# SPECCY2010.net
KiCad netlist of a schematic drawn in Altium Designer
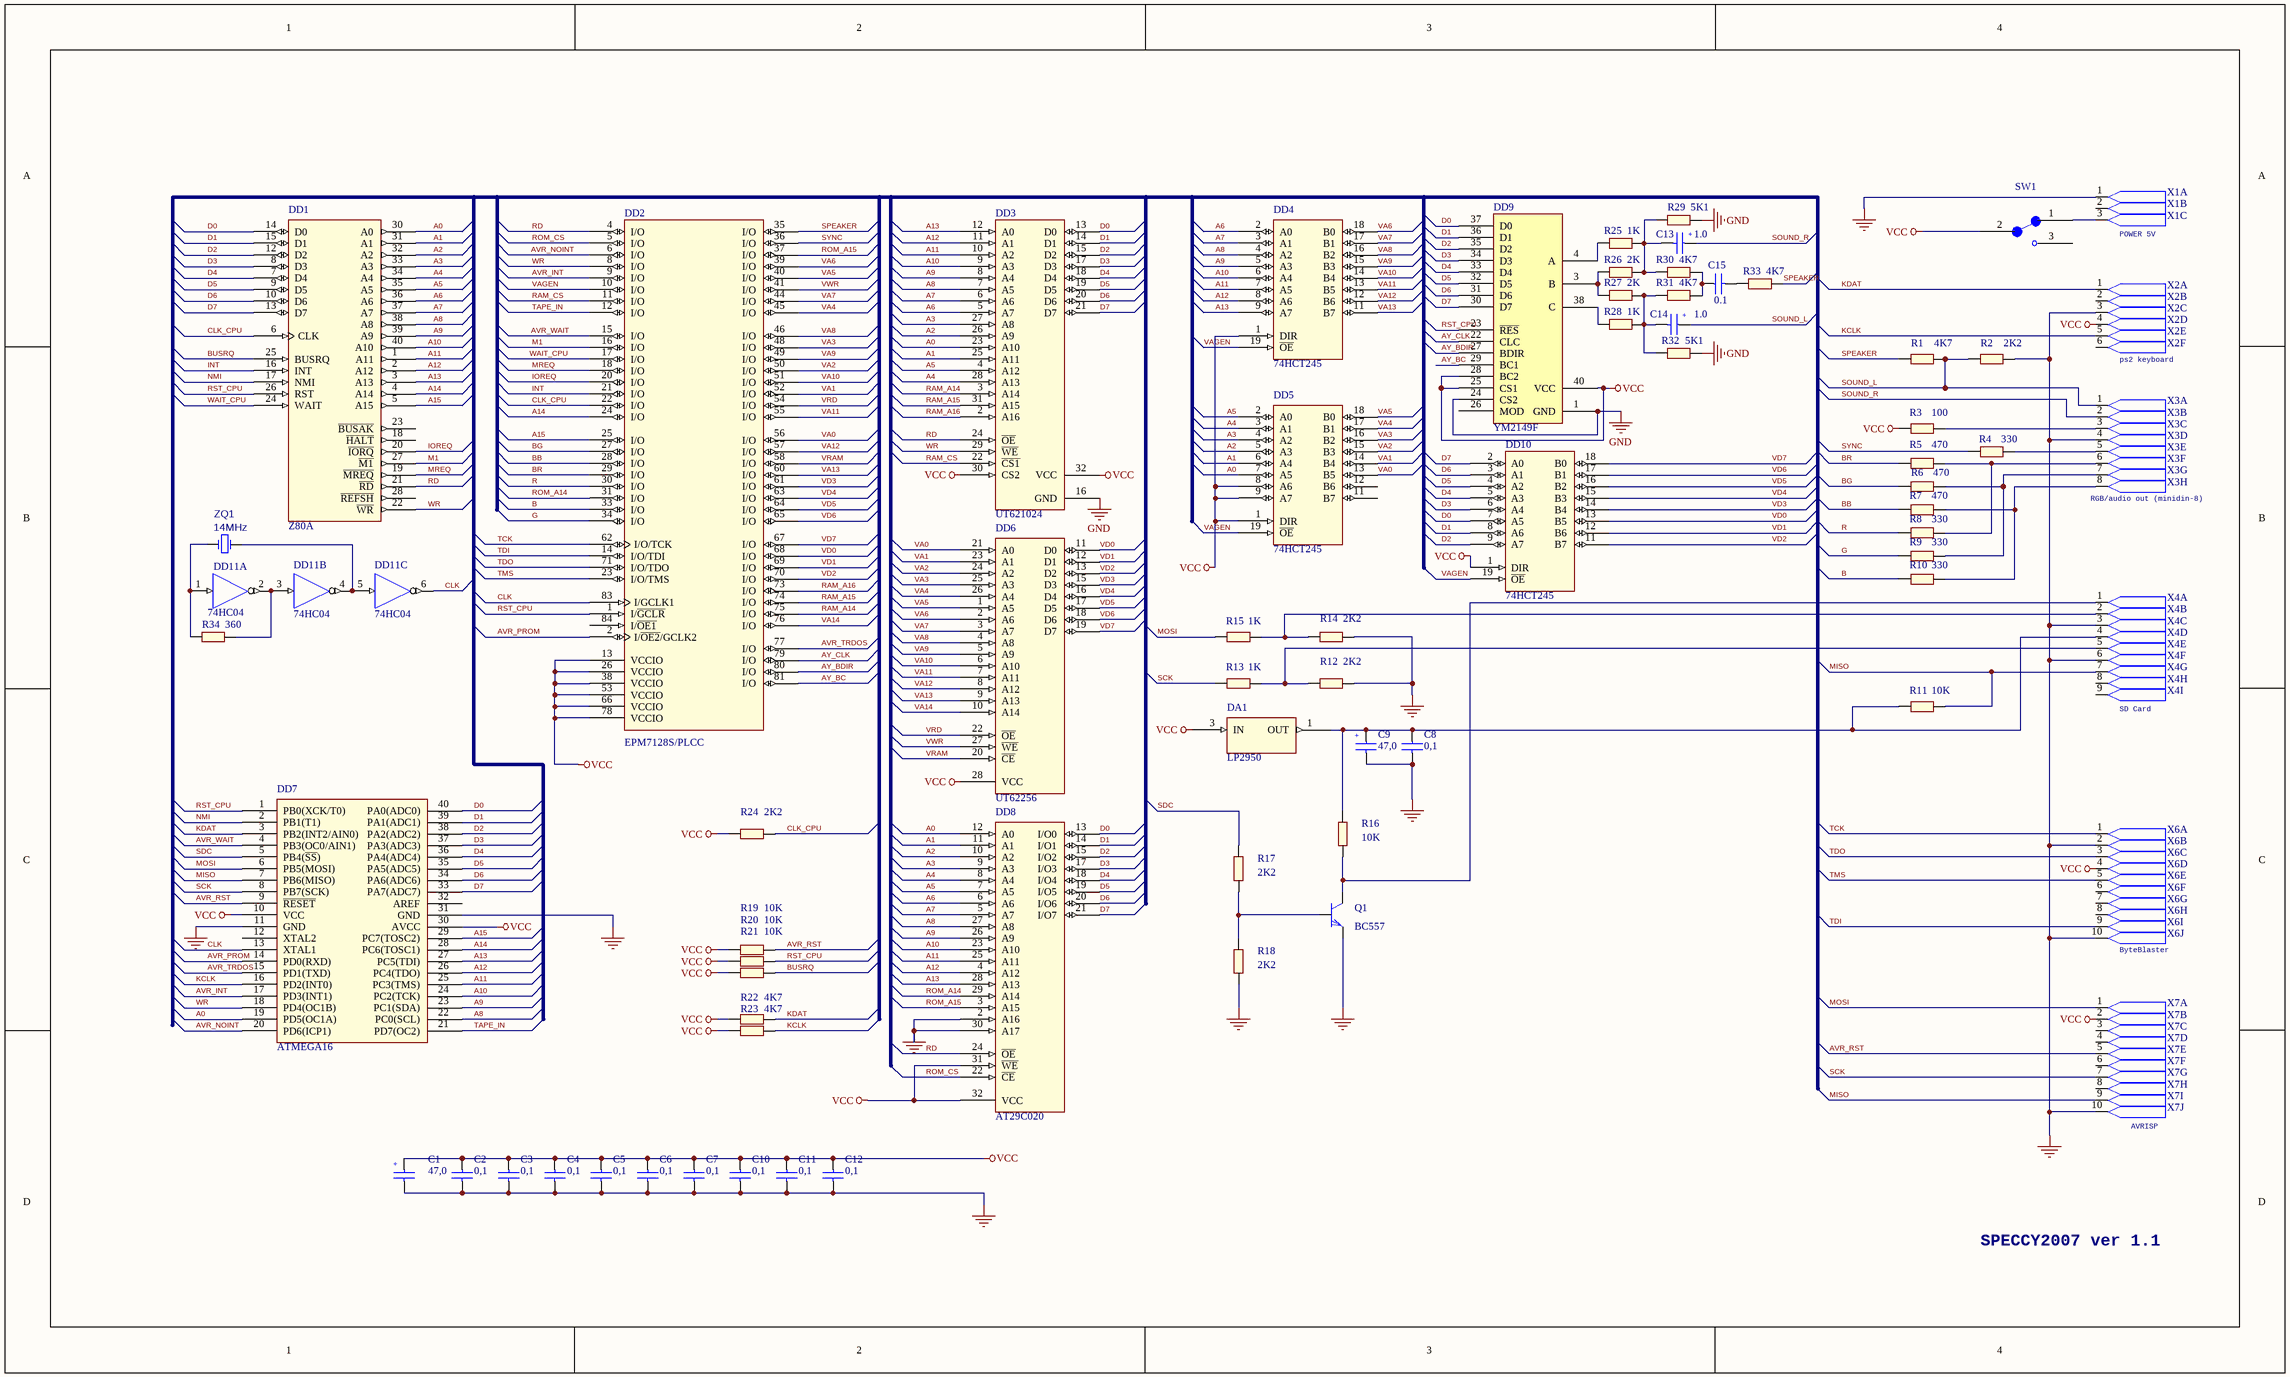
[diagram p0: SPECCY2010.SchDoc]

(export (version "E")
  (design (tool "Eeschema 10.0.6"))
  (components
    (comp (ref "C1")
      (value "47,0")
      (footprint "CAPPOL_2.54")
      (libsource (lib "SPECCY2007_Library") (part "C POL"))
    )
    (comp (ref "C2")
      (value "0,1")
      (footprint "CAP_5.08-7.8x3.2")
      (libsource (lib "SPECCY2007_Library") (part "C"))
    )
    (comp (ref "C3")
      (value "0,1")
      (footprint "CAP_5.08-7.8x3.2")
      (libsource (lib "SPECCY2007_Library") (part "C"))
    )
    (comp (ref "C4")
      (value "0,1")
      (footprint "CAP_5.08-7.8x3.2")
      (libsource (lib "SPECCY2007_Library") (part "C"))
    )
    (comp (ref "C5")
      (value "0,1")
      (footprint "CAP_5.08-7.8x3.2")
      (libsource (lib "SPECCY2007_Library") (part "C"))
    )
    (comp (ref "C6")
      (value "0,1")
      (footprint "CAP_5.08-7.8x3.2")
      (libsource (lib "SPECCY2007_Library") (part "C"))
    )
    (comp (ref "C7")
      (value "0,1")
      (footprint "CAP_5.08-7.8x3.2")
      (libsource (lib "SPECCY2007_Library") (part "C"))
    )
    (comp (ref "C8")
      (value "0,1")
      (footprint "CAP_5.08-7.8x3.2")
      (libsource (lib "SPECCY2007_Library") (part "C"))
    )
    (comp (ref "C9")
      (value "47,0")
      (footprint "CAPPOL_2.54")
      (libsource (lib "SPECCY2007_Library") (part "C POL"))
    )
    (comp (ref "C10")
      (value "0,1")
      (footprint "CAP_5.08-7.8x3.2")
      (libsource (lib "SPECCY2007_Library") (part "C"))
    )
    (comp (ref "C11")
      (value "0,1")
      (footprint "CAP_5.08-7.8x3.2")
      (libsource (lib "SPECCY2007_Library") (part "C"))
    )
    (comp (ref "C12")
      (value "0,1")
      (footprint "CAP_5.08-7.8x3.2")
      (libsource (lib "SPECCY2007_Library") (part "C"))
    )
    (comp (ref "C13")
      (value "1.0")
      (footprint "CAPPOL_2.54")
      (libsource (lib "SPECCY2010_Library") (part "C POL"))
    )
    (comp (ref "C14")
      (value "1.0")
      (footprint "CAPPOL_2.54")
      (libsource (lib "SPECCY2010_Library") (part "C POL"))
    )
    (comp (ref "C15")
      (value "0.1")
      (footprint "CAP_5.08-7.8x3.2")
      (libsource (lib "SPECCY2010_Library") (part "C"))
    )
    (comp (ref "DA1")
      (value "LP2950")
      (footprint "TO92")
      (libsource (lib "SPECCY2007_Library") (part "LP2950"))
    )
    (comp (ref "DD1")
      (value "Z80A")
      (footprint "DIP-40")
      (libsource (lib "SPECCY2007_Library") (part "Z80A"))
    )
    (comp (ref "DD2")
      (value "EPM7128S/PLCC")
      (footprint "PLCC84-Socket+AlteraMAX700S")
      (libsource (lib "SPECCY2007_Library") (part "EPM7128S/PLCC"))
    )
    (comp (ref "DD3")
      (value "UT621024")
      (footprint "DIP-32/D41.2")
      (libsource (lib "SPECCY2010_Library") (part "UT621024"))
    )
    (comp (ref "DD4")
      (value "74HCT245")
      (footprint "DIP-20")
      (libsource (lib "SPECCY2007_Library") (part "74HCT245"))
    )
    (comp (ref "DD5")
      (value "74HCT245")
      (footprint "DIP-20")
      (libsource (lib "SPECCY2007_Library") (part "74HCT245"))
    )
    (comp (ref "DD6")
      (value "UT62256")
      (footprint "DIP-28W")
      (libsource (lib "SPECCY2010_Library") (part "CY62256_Syd's"))
    )
    (comp (ref "DD7")
      (value "ATMEGA16")
      (footprint "DIP-40")
      (libsource (lib "SPECCY2007_Library") (part "ATMEGA16"))
    )
    (comp (ref "DD8")
      (value "AT29C020")
      (footprint "DIP-32/D41.2")
      (libsource (lib "SPECCY2007_Library") (part "AT29C020"))
    )
    (comp (ref "DD9")
      (value "YM2149F")
      (footprint "DIP-40")
      (libsource (lib "SPECCY2010_Library") (part "YM2149F"))
    )
    (comp (ref "DD10")
      (value "74HCT245")
      (footprint "DIP-20")
      (libsource (lib "SPECCY2010_Library") (part "74HCT245"))
    )
    (comp (ref "DD11")
      (value "74HC04")
      (footprint "DIP-14")
      (description "Hex Inverter")
      (fields (field (name "PUBLISHER") "Altium Limited"))
      (libsource (lib "SPECCY2010_Library") (part "74HC04"))
    )
    (comp (ref "Q1")
      (value "BC557")
      (footprint "TO92")
      (libsource (lib "SPECCY2007_Library") (part "TRANS NPN"))
    )
    (comp (ref "R1") (value "4K7") (footprint "RES_10.16") (libsource (lib "") (part "R_1")))
    (comp (ref "R2") (value "2K2") (footprint "RES_10.16") (libsource (lib "") (part "R_1")))
    (comp (ref "R3") (value "100") (footprint "RES_10.16") (libsource (lib "") (part "R_1")))
    (comp (ref "R4") (value "330") (footprint "RES_10.16") (libsource (lib "") (part "R_1")))
    (comp (ref "R5") (value "470") (footprint "RES_10.16") (libsource (lib "") (part "R_1")))
    (comp (ref "R6") (value "470") (footprint "RES_10.16") (libsource (lib "") (part "R_1")))
    (comp (ref "R7") (value "470") (footprint "RES_10.16") (libsource (lib "") (part "R_1")))
    (comp (ref "R8") (value "330") (footprint "RES_10.16") (libsource (lib "") (part "R_1")))
    (comp (ref "R9") (value "330") (footprint "RES_10.16") (libsource (lib "") (part "R_1")))
    (comp (ref "R10") (value "330") (footprint "RES_10.16") (libsource (lib "") (part "R_1")))
    (comp (ref "R11") (value "10K") (footprint "RES_10.16") (libsource (lib "") (part "R_1")))
    (comp (ref "R12") (value "2K2") (footprint "RES_10.16") (libsource (lib "") (part "R_1")))
    (comp (ref "R13") (value "1K") (footprint "RES_10.16") (libsource (lib "") (part "R_1")))
    (comp (ref "R14") (value "2K2") (footprint "RES_10.16") (libsource (lib "") (part "R_1")))
    (comp (ref "R15") (value "1K") (footprint "RES_10.16") (libsource (lib "") (part "R_1")))
    (comp (ref "R16") (value "10K") (footprint "RES_10.16") (libsource (lib "SPECCY2007_Library") (part "R")))
    (comp (ref "R17") (value "2K2") (footprint "RES_10.16") (libsource (lib "SPECCY2007_Library") (part "R")))
    (comp (ref "R18") (value "2K2") (footprint "RES_10.16") (libsource (lib "SPECCY2007_Library") (part "R")))
    (comp (ref "R19") (value "10K") (footprint "RES_10.16") (libsource (lib "") (part "R_1")))
    (comp (ref "R20") (value "10K") (footprint "RES_10.16") (libsource (lib "") (part "R_1")))
    (comp (ref "R21") (value "10K") (footprint "RES_10.16") (libsource (lib "") (part "R_1")))
    (comp (ref "R22") (value "4K7") (footprint "RES_10.16") (libsource (lib "") (part "R_1")))
    (comp (ref "R23") (value "4K7") (footprint "RES_10.16") (libsource (lib "") (part "R_1")))
    (comp (ref "R24") (value "2K2") (footprint "RES_10.16") (libsource (lib "") (part "R_1")))
    (comp (ref "R25") (value "1K") (footprint "RES_10.16") (libsource (lib "SPECCY2010_Library") (part "R")))
    (comp (ref "R26") (value "2K") (footprint "RES_10.16") (libsource (lib "SPECCY2010_Library") (part "R")))
    (comp (ref "R27") (value "2K") (footprint "RES_10.16") (libsource (lib "SPECCY2010_Library") (part "R")))
    (comp (ref "R28") (value "1K") (footprint "RES_10.16") (libsource (lib "SPECCY2010_Library") (part "R")))
    (comp (ref "R29") (value "5K1") (footprint "RES_10.16") (libsource (lib "SPECCY2010_Library") (part "R")))
    (comp (ref "R30") (value "4K7") (footprint "RES_10.16") (libsource (lib "SPECCY2010_Library") (part "R")))
    (comp (ref "R31") (value "4K7") (footprint "RES_10.16") (libsource (lib "SPECCY2010_Library") (part "R")))
    (comp (ref "R32") (value "5K1") (footprint "RES_10.16") (libsource (lib "SPECCY2010_Library") (part "R")))
    (comp (ref "R33") (value "4K7") (footprint "RES_10.16") (libsource (lib "SPECCY2010_Library") (part "R")))
    (comp (ref "R34") (value "360") (footprint "RES_10.16") (libsource (lib "SPECCY2010_Library") (part "R")))
    (comp (ref "SW1")
      (value "SW_T_SPDT")
      (footprint "SW_T_SPDT")
      (libsource (lib "SPECCY2007_Library") (part "SW_T_SPDT"))
    )
    (comp (ref "X1")
      (value "X3")
      (footprint "CONN JACK PWR")
      (libsource (lib "SPECCY2007_Library") (part "X3"))
    )
    (comp (ref "X2") (value "X6") (footprint "Mini-DIN6") (libsource (lib "SPECCY2007_Library") (part "X6")))
    (comp (ref "X3") (value "X8") (footprint "Mini-DIN8") (libsource (lib "SPECCY2007_Library") (part "X8")))
    (comp (ref "X4")
      (value "X9")
      (footprint "SD Card socket")
      (description "SD Card socket")
      (libsource (lib "SPECCY2007_Library") (part "X9"))
    )
    (comp (ref "X6")
      (value "X10")
      (footprint "Double row pin strip 5 way")
      (libsource (lib "SPECCY2007_Library") (part "X10"))
    )
    (comp (ref "X7")
      (value "X10")
      (footprint "Double row pin strip 5 way")
      (libsource (lib "SPECCY2007_Library") (part "X10"))
    )
    (comp (ref "ZQ1")
      (value "14MHz")
      (footprint "QUARTZ")
      (description "QUARTZ")
      (libsource (lib "SPECCY2010_Library") (part "QUARTZ"))
    )
  )
  (nets
    (net (code "1") (name "/A0") (class "Default")
      (node (ref "DD1") (pin "30") (pinfunction "A0_30") (pintype "output"))
      (node (ref "DD3") (pin "23") (pinfunction "A10_23") (pintype "input"))
      (node (ref "DD5") (pin "7") (pinfunction "A5_7") (pintype "bidirectional"))
      (node (ref "DD7") (pin "19") (pinfunction "PD5(OC1A)_19") (pintype "passive"))
      (node (ref "DD8") (pin "12") (pinfunction "A0_12") (pintype "input"))
    )
    (net (code "2") (name "/A1") (class "Default")
      (node (ref "DD1") (pin "31") (pinfunction "A1_31") (pintype "output"))
      (node (ref "DD3") (pin "25") (pinfunction "A11_25") (pintype "input"))
      (node (ref "DD5") (pin "6") (pinfunction "A4_6") (pintype "bidirectional"))
      (node (ref "DD8") (pin "11") (pinfunction "A1_11") (pintype "input"))
    )
    (net (code "3") (name "/A2") (class "Default")
      (node (ref "DD1") (pin "32") (pinfunction "A2_32") (pintype "output"))
      (node (ref "DD3") (pin "26") (pinfunction "A9_26") (pintype "input"))
      (node (ref "DD5") (pin "5") (pinfunction "A3_5") (pintype "bidirectional"))
      (node (ref "DD8") (pin "10") (pinfunction "A2_10") (pintype "input"))
    )
    (net (code "4") (name "/A3") (class "Default")
      (node (ref "DD1") (pin "33") (pinfunction "A3_33") (pintype "output"))
      (node (ref "DD3") (pin "27") (pinfunction "A8_27") (pintype "input"))
      (node (ref "DD5") (pin "4") (pinfunction "A2_4") (pintype "bidirectional"))
      (node (ref "DD8") (pin "9") (pinfunction "A3_9") (pintype "input"))
    )
    (net (code "5") (name "/A4") (class "Default")
      (node (ref "DD1") (pin "34") (pinfunction "A4_34") (pintype "output"))
      (node (ref "DD3") (pin "28") (pinfunction "A13_28") (pintype "input"))
      (node (ref "DD5") (pin "3") (pinfunction "A1_3") (pintype "bidirectional"))
      (node (ref "DD8") (pin "8") (pinfunction "A4_8") (pintype "input"))
    )
    (net (code "6") (name "/A5") (class "Default")
      (node (ref "DD1") (pin "35") (pinfunction "A5_35") (pintype "output"))
      (node (ref "DD3") (pin "4") (pinfunction "A12_4") (pintype "input"))
      (node (ref "DD5") (pin "2") (pinfunction "A0_2") (pintype "bidirectional"))
      (node (ref "DD8") (pin "7") (pinfunction "A5_7") (pintype "input"))
    )
    (net (code "7") (name "/A6") (class "Default")
      (node (ref "DD1") (pin "36") (pinfunction "A6_36") (pintype "output"))
      (node (ref "DD3") (pin "5") (pinfunction "A7_5") (pintype "input"))
      (node (ref "DD4") (pin "2") (pinfunction "A0_2") (pintype "bidirectional"))
      (node (ref "DD8") (pin "6") (pinfunction "A6_6") (pintype "input"))
    )
    (net (code "8") (name "/A7") (class "Default")
      (node (ref "DD1") (pin "37") (pinfunction "A7_37") (pintype "output"))
      (node (ref "DD3") (pin "6") (pinfunction "A6_6") (pintype "input"))
      (node (ref "DD4") (pin "3") (pinfunction "A1_3") (pintype "bidirectional"))
      (node (ref "DD8") (pin "5") (pinfunction "A7_5") (pintype "input"))
    )
    (net (code "9") (name "/A8") (class "Default")
      (node (ref "DD1") (pin "38") (pinfunction "A8_38") (pintype "output"))
      (node (ref "DD3") (pin "7") (pinfunction "A5_7") (pintype "input"))
      (node (ref "DD4") (pin "4") (pinfunction "A2_4") (pintype "bidirectional"))
      (node (ref "DD7") (pin "22") (pinfunction "PC0(SCL)_22") (pintype "passive"))
      (node (ref "DD8") (pin "27") (pinfunction "A8_27") (pintype "input"))
    )
    (net (code "10") (name "/A9") (class "Default")
      (node (ref "DD1") (pin "39") (pinfunction "A9_39") (pintype "output"))
      (node (ref "DD3") (pin "8") (pinfunction "A4_8") (pintype "input"))
      (node (ref "DD4") (pin "5") (pinfunction "A3_5") (pintype "bidirectional"))
      (node (ref "DD7") (pin "23") (pinfunction "PC1(SDA)_23") (pintype "passive"))
      (node (ref "DD8") (pin "26") (pinfunction "A9_26") (pintype "input"))
    )
    (net (code "11") (name "/A10") (class "Default")
      (node (ref "DD1") (pin "40") (pinfunction "A10_40") (pintype "output"))
      (node (ref "DD3") (pin "9") (pinfunction "A3_9") (pintype "input"))
      (node (ref "DD4") (pin "6") (pinfunction "A4_6") (pintype "bidirectional"))
      (node (ref "DD7") (pin "24") (pinfunction "PC2(TCK)_24") (pintype "passive"))
      (node (ref "DD8") (pin "23") (pinfunction "A10_23") (pintype "input"))
    )
    (net (code "12") (name "/A11") (class "Default")
      (node (ref "DD1") (pin "1") (pinfunction "A11_1") (pintype "output"))
      (node (ref "DD3") (pin "10") (pinfunction "A2_10") (pintype "input"))
      (node (ref "DD4") (pin "7") (pinfunction "A5_7") (pintype "bidirectional"))
      (node (ref "DD7") (pin "25") (pinfunction "PC3(TMS)_25") (pintype "passive"))
      (node (ref "DD8") (pin "25") (pinfunction "A11_25") (pintype "input"))
    )
    (net (code "13") (name "/A12") (class "Default")
      (node (ref "DD1") (pin "2") (pinfunction "A12_2") (pintype "output"))
      (node (ref "DD3") (pin "11") (pinfunction "A1_11") (pintype "input"))
      (node (ref "DD4") (pin "8") (pinfunction "A6_8") (pintype "bidirectional"))
      (node (ref "DD7") (pin "26") (pinfunction "PC4(TDO)_26") (pintype "passive"))
      (node (ref "DD8") (pin "4") (pinfunction "A12_4") (pintype "input"))
    )
    (net (code "14") (name "/A13") (class "Default")
      (node (ref "DD1") (pin "3") (pinfunction "A13_3") (pintype "output"))
      (node (ref "DD3") (pin "12") (pinfunction "A0_12") (pintype "input"))
      (node (ref "DD4") (pin "9") (pinfunction "A7_9") (pintype "bidirectional"))
      (node (ref "DD7") (pin "27") (pinfunction "PC5(TDI)_27") (pintype "passive"))
      (node (ref "DD8") (pin "28") (pinfunction "A13_28") (pintype "input"))
    )
    (net (code "15") (name "/A14") (class "Default")
      (node (ref "DD1") (pin "4") (pinfunction "A14_4") (pintype "output"))
      (node (ref "DD2") (pin "24") (pinfunction "I/O_24") (pintype "bidirectional"))
      (node (ref "DD7") (pin "28") (pinfunction "PC6(TOSC1)_28") (pintype "passive"))
    )
    (net (code "16") (name "/A15") (class "Default")
      (node (ref "DD1") (pin "5") (pinfunction "A15_5") (pintype "output"))
      (node (ref "DD2") (pin "25") (pinfunction "I/O_25") (pintype "bidirectional"))
      (node (ref "DD7") (pin "29") (pinfunction "PC7(TOSC2)_29") (pintype "passive"))
    )
    (net (code "17") (name "/AVR_INT") (class "Default")
      (node (ref "DD2") (pin "9") (pinfunction "I/O_9") (pintype "bidirectional"))
      (node (ref "DD7") (pin "17") (pinfunction "PD3(INT1)_17") (pintype "passive"))
    )
    (net (code "18") (name "/AVR_NOINT") (class "Default")
      (node (ref "DD2") (pin "6") (pinfunction "I/O_6") (pintype "bidirectional"))
      (node (ref "DD7") (pin "20") (pinfunction "PD6(ICP1)_20") (pintype "passive"))
    )
    (net (code "19") (name "/AVR_PROM") (class "Default")
      (node (ref "DD2") (pin "2") (pinfunction "I/~{OE2}/GCLK2_2") (pintype "bidirectional"))
      (node (ref "DD7") (pin "14") (pinfunction "PD0(RXD)_14") (pintype "passive"))
    )
    (net (code "20") (name "/AVR_RST") (class "Default")
      (node (ref "DD7") (pin "9") (pinfunction "~{RESET}_9") (pintype "passive"))
      (node (ref "R19") (pin "2") (pinfunction "2_2") (pintype "passive"))
      (node (ref "X7") (pin "5") (pinfunction "CON_5") (pintype "passive"))
    )
    (net (code "21") (name "/AVR_TRDOS") (class "Default")
      (node (ref "DD2") (pin "77") (pinfunction "I/O_77") (pintype "bidirectional"))
      (node (ref "DD7") (pin "15") (pinfunction "PD1(TXD)_15") (pintype "passive"))
    )
    (net (code "22") (name "/AVR_WAIT") (class "Default")
      (node (ref "DD2") (pin "15") (pinfunction "I/O_15") (pintype "bidirectional"))
      (node (ref "DD7") (pin "4") (pinfunction "PB3(OC0/AIN1)_4") (pintype "passive"))
    )
    (net (code "23") (name "/AY_BC") (class "Default")
      (node (ref "DD2") (pin "81") (pinfunction "I/O_81") (pintype "bidirectional"))
      (node (ref "DD9") (pin "29") (pinfunction "BC1_29") (pintype "passive"))
    )
    (net (code "24") (name "/AY_BDIR") (class "Default")
      (node (ref "DD2") (pin "80") (pinfunction "I/O_80") (pintype "bidirectional"))
      (node (ref "DD9") (pin "27") (pinfunction "BDIR_27") (pintype "passive"))
    )
    (net (code "25") (name "/AY_CLK") (class "Default")
      (node (ref "DD2") (pin "79") (pinfunction "I/O_79") (pintype "bidirectional"))
      (node (ref "DD9") (pin "22") (pinfunction "CLC_22") (pintype "passive"))
    )
    (net (code "26") (name "/B") (class "Default")
      (node (ref "DD2") (pin "33") (pinfunction "I/O_33") (pintype "bidirectional"))
      (node (ref "R10") (pin "1") (pinfunction "1_1") (pintype "passive"))
    )
    (net (code "27") (name "/BB") (class "Default")
      (node (ref "DD2") (pin "28") (pinfunction "I/O_28") (pintype "bidirectional"))
      (node (ref "R7") (pin "1") (pinfunction "1_1") (pintype "passive"))
    )
    (net (code "28") (name "/BG") (class "Default")
      (node (ref "DD2") (pin "27") (pinfunction "I/O_27") (pintype "bidirectional"))
      (node (ref "R6") (pin "1") (pinfunction "1_1") (pintype "passive"))
    )
    (net (code "29") (name "/BR") (class "Default")
      (node (ref "DD2") (pin "29") (pinfunction "I/O_29") (pintype "bidirectional"))
      (node (ref "R5") (pin "1") (pinfunction "1_1") (pintype "passive"))
    )
    (net (code "30") (name "/BUSRQ") (class "Default")
      (node (ref "DD1") (pin "25") (pinfunction "BUSRQ_25") (pintype "input"))
      (node (ref "R21") (pin "2") (pinfunction "2_2") (pintype "passive"))
    )
    (net (code "31") (name "/CLK") (class "Default")
      (node (ref "DD11") (pin "6") (pinfunction "Y_6") (pintype "output"))
      (node (ref "DD2") (pin "83") (pinfunction "I/GCLK1_83") (pintype "input"))
      (node (ref "DD7") (pin "13") (pinfunction "XTAL1_13") (pintype "passive"))
    )
    (net (code "32") (name "/CLK_CPU") (class "Default")
      (node (ref "DD1") (pin "6") (pinfunction "CLK_6") (pintype "input"))
      (node (ref "DD2") (pin "22") (pinfunction "I/O_22") (pintype "bidirectional"))
      (node (ref "R24") (pin "2") (pinfunction "2_2") (pintype "passive"))
    )
    (net (code "33") (name "/D0") (class "Default")
      (node (ref "DD1") (pin "14") (pinfunction "D0_14") (pintype "bidirectional"))
      (node (ref "DD10") (pin "7") (pinfunction "A5_7") (pintype "bidirectional"))
      (node (ref "DD3") (pin "13") (pinfunction "D0_13") (pintype "bidirectional"))
      (node (ref "DD7") (pin "40") (pinfunction "PA0(ADC0)_40") (pintype "passive"))
      (node (ref "DD8") (pin "13") (pinfunction "I/O0_13") (pintype "bidirectional"))
      (node (ref "DD9") (pin "37") (pinfunction "D0_37") (pintype "passive"))
    )
    (net (code "34") (name "/D1") (class "Default")
      (node (ref "DD1") (pin "15") (pinfunction "D1_15") (pintype "bidirectional"))
      (node (ref "DD10") (pin "8") (pinfunction "A6_8") (pintype "bidirectional"))
      (node (ref "DD3") (pin "14") (pinfunction "D1_14") (pintype "bidirectional"))
      (node (ref "DD7") (pin "39") (pinfunction "PA1(ADC1)_39") (pintype "passive"))
      (node (ref "DD8") (pin "14") (pinfunction "I/O1_14") (pintype "bidirectional"))
      (node (ref "DD9") (pin "36") (pinfunction "D1_36") (pintype "passive"))
    )
    (net (code "35") (name "/D2") (class "Default")
      (node (ref "DD1") (pin "12") (pinfunction "D2_12") (pintype "bidirectional"))
      (node (ref "DD10") (pin "9") (pinfunction "A7_9") (pintype "bidirectional"))
      (node (ref "DD3") (pin "15") (pinfunction "D2_15") (pintype "bidirectional"))
      (node (ref "DD7") (pin "38") (pinfunction "PA2(ADC2)_38") (pintype "passive"))
      (node (ref "DD8") (pin "15") (pinfunction "I/O2_15") (pintype "bidirectional"))
      (node (ref "DD9") (pin "35") (pinfunction "D2_35") (pintype "passive"))
    )
    (net (code "36") (name "/D3") (class "Default")
      (node (ref "DD1") (pin "8") (pinfunction "D3_8") (pintype "bidirectional"))
      (node (ref "DD10") (pin "6") (pinfunction "A4_6") (pintype "bidirectional"))
      (node (ref "DD3") (pin "17") (pinfunction "D3_17") (pintype "bidirectional"))
      (node (ref "DD7") (pin "37") (pinfunction "PA3(ADC3)_37") (pintype "passive"))
      (node (ref "DD8") (pin "17") (pinfunction "I/O3_17") (pintype "bidirectional"))
      (node (ref "DD9") (pin "34") (pinfunction "D3_34") (pintype "passive"))
    )
    (net (code "37") (name "/D4") (class "Default")
      (node (ref "DD1") (pin "7") (pinfunction "D4_7") (pintype "bidirectional"))
      (node (ref "DD10") (pin "5") (pinfunction "A3_5") (pintype "bidirectional"))
      (node (ref "DD3") (pin "18") (pinfunction "D4_18") (pintype "bidirectional"))
      (node (ref "DD7") (pin "36") (pinfunction "PA4(ADC4)_36") (pintype "passive"))
      (node (ref "DD8") (pin "18") (pinfunction "I/O4_18") (pintype "bidirectional"))
      (node (ref "DD9") (pin "33") (pinfunction "D4_33") (pintype "passive"))
    )
    (net (code "38") (name "/D5") (class "Default")
      (node (ref "DD1") (pin "9") (pinfunction "D5_9") (pintype "bidirectional"))
      (node (ref "DD10") (pin "4") (pinfunction "A2_4") (pintype "bidirectional"))
      (node (ref "DD3") (pin "19") (pinfunction "D5_19") (pintype "bidirectional"))
      (node (ref "DD7") (pin "35") (pinfunction "PA5(ADC5)_35") (pintype "passive"))
      (node (ref "DD8") (pin "19") (pinfunction "I/O5_19") (pintype "bidirectional"))
      (node (ref "DD9") (pin "32") (pinfunction "D5_32") (pintype "passive"))
    )
    (net (code "39") (name "/D6") (class "Default")
      (node (ref "DD1") (pin "10") (pinfunction "D6_10") (pintype "bidirectional"))
      (node (ref "DD10") (pin "3") (pinfunction "A1_3") (pintype "bidirectional"))
      (node (ref "DD3") (pin "20") (pinfunction "D6_20") (pintype "bidirectional"))
      (node (ref "DD7") (pin "34") (pinfunction "PA6(ADC6)_34") (pintype "passive"))
      (node (ref "DD8") (pin "20") (pinfunction "I/O6_20") (pintype "bidirectional"))
      (node (ref "DD9") (pin "31") (pinfunction "D6_31") (pintype "passive"))
    )
    (net (code "40") (name "/D7") (class "Default")
      (node (ref "DD1") (pin "13") (pinfunction "D7_13") (pintype "bidirectional"))
      (node (ref "DD10") (pin "2") (pinfunction "A0_2") (pintype "bidirectional"))
      (node (ref "DD3") (pin "21") (pinfunction "D7_21") (pintype "bidirectional"))
      (node (ref "DD7") (pin "33") (pinfunction "PA7(ADC7)_33") (pintype "passive"))
      (node (ref "DD8") (pin "21") (pinfunction "I/O7_21") (pintype "bidirectional"))
      (node (ref "DD9") (pin "30") (pinfunction "D7_30") (pintype "passive"))
    )
    (net (code "41") (name "/G") (class "Default")
      (node (ref "DD2") (pin "34") (pinfunction "I/O_34") (pintype "bidirectional"))
      (node (ref "R9") (pin "1") (pinfunction "1_1") (pintype "passive"))
    )
    (net (code "42") (name "/INT") (class "Default")
      (node (ref "DD1") (pin "16") (pinfunction "INT_16") (pintype "input"))
      (node (ref "DD2") (pin "21") (pinfunction "I/O_21") (pintype "bidirectional"))
    )
    (net (code "43") (name "/IOREQ") (class "Default")
      (node (ref "DD1") (pin "20") (pinfunction "~{IORQ}_20") (pintype "output"))
      (node (ref "DD2") (pin "20") (pinfunction "I/O_20") (pintype "bidirectional"))
    )
    (net (code "44") (name "/KCLK") (class "Default")
      (node (ref "DD7") (pin "16") (pinfunction "PD2(INT0)_16") (pintype "passive"))
      (node (ref "R23") (pin "2") (pinfunction "2_2") (pintype "passive"))
      (node (ref "X2") (pin "5") (pinfunction "CON_5") (pintype "passive"))
    )
    (net (code "45") (name "/KDAT") (class "Default")
      (node (ref "DD7") (pin "3") (pinfunction "PB2(INT2/AIN0)_3") (pintype "passive"))
      (node (ref "R22") (pin "2") (pinfunction "2_2") (pintype "passive"))
      (node (ref "X2") (pin "1") (pinfunction "CON_1") (pintype "passive"))
    )
    (net (code "46") (name "/M1") (class "Default")
      (node (ref "DD1") (pin "27") (pinfunction "~{M1}_27") (pintype "output"))
      (node (ref "DD2") (pin "16") (pinfunction "I/O_16") (pintype "bidirectional"))
    )
    (net (code "47") (name "/MISO") (class "Default")
      (node (ref "DD7") (pin "7") (pinfunction "PB6(MISO)_7") (pintype "passive"))
      (node (ref "R11") (pin "2") (pinfunction "2_2") (pintype "passive"))
      (node (ref "X4") (pin "7") (pinfunction "CON_7") (pintype "passive"))
      (node (ref "X7") (pin "9") (pinfunction "CON_9") (pintype "passive"))
    )
    (net (code "48") (name "/MOSI") (class "Default")
      (node (ref "DD7") (pin "6") (pinfunction "PB5(MOSI)_6") (pintype "passive"))
      (node (ref "R15") (pin "1") (pinfunction "1_1") (pintype "passive"))
      (node (ref "X7") (pin "1") (pinfunction "CON_1") (pintype "passive"))
    )
    (net (code "49") (name "/MREQ") (class "Default")
      (node (ref "DD1") (pin "19") (pinfunction "~{MREQ}_19") (pintype "output"))
      (node (ref "DD2") (pin "18") (pinfunction "I/O_18") (pintype "bidirectional"))
    )
    (net (code "50") (name "/NMI") (class "Default")
      (node (ref "DD1") (pin "17") (pinfunction "NMI_17") (pintype "input"))
      (node (ref "DD7") (pin "2") (pinfunction "PB1(T1)_2") (pintype "passive"))
    )
    (net (code "51") (name "/R") (class "Default")
      (node (ref "DD2") (pin "30") (pinfunction "I/O_30") (pintype "bidirectional"))
      (node (ref "R8") (pin "1") (pinfunction "1_1") (pintype "passive"))
    )
    (net (code "52") (name "/RAM_A14") (class "Default")
      (node (ref "DD2") (pin "75") (pinfunction "I/O_75") (pintype "bidirectional"))
      (node (ref "DD3") (pin "3") (pinfunction "A14_3") (pintype "input"))
    )
    (net (code "53") (name "/RAM_A15") (class "Default")
      (node (ref "DD2") (pin "74") (pinfunction "I/O_74") (pintype "bidirectional"))
      (node (ref "DD3") (pin "31") (pinfunction "A15_31") (pintype "input"))
    )
    (net (code "54") (name "/RAM_A16") (class "Default")
      (node (ref "DD2") (pin "73") (pinfunction "I/O_73") (pintype "bidirectional"))
      (node (ref "DD3") (pin "2") (pinfunction "A16_2") (pintype "input"))
    )
    (net (code "55") (name "/RAM_CS") (class "Default")
      (node (ref "DD2") (pin "11") (pinfunction "I/O_11") (pintype "bidirectional"))
      (node (ref "DD3") (pin "22") (pinfunction "~{CS1}_22") (pintype "input"))
    )
    (net (code "56") (name "/RD") (class "Default")
      (node (ref "DD1") (pin "21") (pinfunction "~{RD}_21") (pintype "output"))
      (node (ref "DD2") (pin "4") (pinfunction "I/O_4") (pintype "bidirectional"))
      (node (ref "DD3") (pin "24") (pinfunction "~{OE}_24") (pintype "input"))
      (node (ref "DD8") (pin "24") (pinfunction "~{OE}_24") (pintype "input"))
    )
    (net (code "57") (name "/ROM_A14") (class "Default")
      (node (ref "DD2") (pin "31") (pinfunction "I/O_31") (pintype "bidirectional"))
      (node (ref "DD8") (pin "29") (pinfunction "A14_29") (pintype "input"))
    )
    (net (code "58") (name "/ROM_A15") (class "Default")
      (node (ref "DD2") (pin "37") (pinfunction "I/O_37") (pintype "bidirectional"))
      (node (ref "DD8") (pin "3") (pinfunction "A15_3") (pintype "input"))
    )
    (net (code "59") (name "/ROM_CS") (class "Default")
      (node (ref "DD2") (pin "5") (pinfunction "I/O_5") (pintype "bidirectional"))
      (node (ref "DD8") (pin "22") (pinfunction "~{CE}_22") (pintype "input"))
    )
    (net (code "60") (name "/RST_CPU") (class "Default")
      (node (ref "DD1") (pin "26") (pinfunction "RST_26") (pintype "input"))
      (node (ref "DD2") (pin "1") (pinfunction "I/~{GCLR}_1") (pintype "input"))
      (node (ref "DD7") (pin "1") (pinfunction "PB0(XCK/T0)_1") (pintype "passive"))
      (node (ref "DD9") (pin "23") (pinfunction "~{RES}_23") (pintype "passive"))
      (node (ref "R20") (pin "2") (pinfunction "2_2") (pintype "passive"))
    )
    (net (code "61") (name "/SCK") (class "Default")
      (node (ref "DD7") (pin "8") (pinfunction "PB7(SCK)_8") (pintype "passive"))
      (node (ref "R13") (pin "1") (pinfunction "1_1") (pintype "passive"))
      (node (ref "X7") (pin "7") (pinfunction "CON_7") (pintype "passive"))
    )
    (net (code "62") (name "/SDC") (class "Default")
      (node (ref "DD7") (pin "5") (pinfunction "PB4(~{SS})_5") (pintype "passive"))
      (node (ref "R17") (pin "2") (pinfunction "2_2") (pintype "passive"))
    )
    (net (code "63") (name "/SOUND_L") (class "Default")
      (node (ref "C14") (pin "PLUS") (pinfunction "PLUS_PLUS") (pintype "passive"))
      (node (ref "R1") (pin "2") (pinfunction "2_2") (pintype "passive"))
      (node (ref "R2") (pin "1") (pinfunction "1_1") (pintype "passive"))
      (node (ref "X3") (pin "1") (pinfunction "CON_1") (pintype "passive"))
    )
    (net (code "64") (name "/SOUND_R") (class "Default")
      (node (ref "C13") (pin "PLUS") (pinfunction "PLUS_PLUS") (pintype "passive"))
      (node (ref "X3") (pin "2") (pinfunction "CON_2") (pintype "passive"))
    )
    (net (code "65") (name "/SPEAKER") (class "Default")
      (node (ref "DD2") (pin "35") (pinfunction "I/O_35") (pintype "bidirectional"))
      (node (ref "R1") (pin "1") (pinfunction "1_1") (pintype "passive"))
      (node (ref "R33") (pin "2") (pinfunction "2_2") (pintype "passive"))
    )
    (net (code "66") (name "/SYNC") (class "Default")
      (node (ref "DD2") (pin "36") (pinfunction "I/O_36") (pintype "bidirectional"))
      (node (ref "R4") (pin "1") (pinfunction "1_1") (pintype "passive"))
    )
    (net (code "67") (name "/TAPE_IN") (class "Default")
      (node (ref "DD2") (pin "12") (pinfunction "I/O_12") (pintype "bidirectional"))
      (node (ref "DD7") (pin "21") (pinfunction "PD7(OC2)_21") (pintype "passive"))
    )
    (net (code "68") (name "/TCK") (class "Default")
      (node (ref "DD2") (pin "62") (pinfunction "I/O/TCK_62") (pintype "bidirectional"))
      (node (ref "X6") (pin "1") (pinfunction "CON_1") (pintype "passive"))
    )
    (net (code "69") (name "/TDI") (class "Default")
      (node (ref "DD2") (pin "14") (pinfunction "I/O/TDI_14") (pintype "bidirectional"))
      (node (ref "X6") (pin "9") (pinfunction "CON_9") (pintype "passive"))
    )
    (net (code "70") (name "/TDO") (class "Default")
      (node (ref "DD2") (pin "71") (pinfunction "I/O/TDO_71") (pintype "bidirectional"))
      (node (ref "X6") (pin "3") (pinfunction "CON_3") (pintype "passive"))
    )
    (net (code "71") (name "/TMS") (class "Default")
      (node (ref "DD2") (pin "23") (pinfunction "I/O/TMS_23") (pintype "bidirectional"))
      (node (ref "X6") (pin "5") (pinfunction "CON_5") (pintype "passive"))
    )
    (net (code "72") (name "/VA0") (class "Default")
      (node (ref "DD2") (pin "56") (pinfunction "I/O_56") (pintype "bidirectional"))
      (node (ref "DD5") (pin "13") (pinfunction "B5_13") (pintype "bidirectional"))
      (node (ref "DD6") (pin "21") (pinfunction "A0_21") (pintype "input"))
    )
    (net (code "73") (name "/VA1") (class "Default")
      (node (ref "DD2") (pin "52") (pinfunction "I/O_52") (pintype "bidirectional"))
      (node (ref "DD5") (pin "14") (pinfunction "B4_14") (pintype "bidirectional"))
      (node (ref "DD6") (pin "23") (pinfunction "A1_23") (pintype "input"))
    )
    (net (code "74") (name "/VA2") (class "Default")
      (node (ref "DD2") (pin "50") (pinfunction "I/O_50") (pintype "bidirectional"))
      (node (ref "DD5") (pin "15") (pinfunction "B3_15") (pintype "bidirectional"))
      (node (ref "DD6") (pin "24") (pinfunction "A2_24") (pintype "input"))
    )
    (net (code "75") (name "/VA3") (class "Default")
      (node (ref "DD2") (pin "48") (pinfunction "I/O_48") (pintype "bidirectional"))
      (node (ref "DD5") (pin "16") (pinfunction "B2_16") (pintype "bidirectional"))
      (node (ref "DD6") (pin "25") (pinfunction "A3_25") (pintype "input"))
    )
    (net (code "76") (name "/VA4") (class "Default")
      (node (ref "DD2") (pin "45") (pinfunction "I/O_45") (pintype "bidirectional"))
      (node (ref "DD5") (pin "17") (pinfunction "B1_17") (pintype "bidirectional"))
      (node (ref "DD6") (pin "26") (pinfunction "A4_26") (pintype "input"))
    )
    (net (code "77") (name "/VA5") (class "Default")
      (node (ref "DD2") (pin "40") (pinfunction "I/O_40") (pintype "bidirectional"))
      (node (ref "DD5") (pin "18") (pinfunction "B0_18") (pintype "bidirectional"))
      (node (ref "DD6") (pin "1") (pinfunction "A5_1") (pintype "input"))
    )
    (net (code "78") (name "/VA6") (class "Default")
      (node (ref "DD2") (pin "39") (pinfunction "I/O_39") (pintype "bidirectional"))
      (node (ref "DD4") (pin "18") (pinfunction "B0_18") (pintype "bidirectional"))
      (node (ref "DD6") (pin "2") (pinfunction "A6_2") (pintype "input"))
    )
    (net (code "79") (name "/VA7") (class "Default")
      (node (ref "DD2") (pin "44") (pinfunction "I/O_44") (pintype "bidirectional"))
      (node (ref "DD4") (pin "17") (pinfunction "B1_17") (pintype "bidirectional"))
      (node (ref "DD6") (pin "3") (pinfunction "A7_3") (pintype "input"))
    )
    (net (code "80") (name "/VA8") (class "Default")
      (node (ref "DD2") (pin "46") (pinfunction "I/O_46") (pintype "bidirectional"))
      (node (ref "DD4") (pin "16") (pinfunction "B2_16") (pintype "bidirectional"))
      (node (ref "DD6") (pin "4") (pinfunction "A8_4") (pintype "input"))
    )
    (net (code "81") (name "/VA9") (class "Default")
      (node (ref "DD2") (pin "49") (pinfunction "I/O_49") (pintype "bidirectional"))
      (node (ref "DD4") (pin "15") (pinfunction "B3_15") (pintype "bidirectional"))
      (node (ref "DD6") (pin "5") (pinfunction "A9_5") (pintype "input"))
    )
    (net (code "82") (name "/VA10") (class "Default")
      (node (ref "DD2") (pin "51") (pinfunction "I/O_51") (pintype "bidirectional"))
      (node (ref "DD4") (pin "14") (pinfunction "B4_14") (pintype "bidirectional"))
      (node (ref "DD6") (pin "6") (pinfunction "A10_6") (pintype "input"))
    )
    (net (code "83") (name "/VA11") (class "Default")
      (node (ref "DD2") (pin "55") (pinfunction "I/O_55") (pintype "bidirectional"))
      (node (ref "DD4") (pin "13") (pinfunction "B5_13") (pintype "bidirectional"))
      (node (ref "DD6") (pin "7") (pinfunction "A11_7") (pintype "input"))
    )
    (net (code "84") (name "/VA12") (class "Default")
      (node (ref "DD2") (pin "57") (pinfunction "I/O_57") (pintype "bidirectional"))
      (node (ref "DD4") (pin "12") (pinfunction "B6_12") (pintype "bidirectional"))
      (node (ref "DD6") (pin "8") (pinfunction "A12_8") (pintype "input"))
    )
    (net (code "85") (name "/VA13") (class "Default")
      (node (ref "DD2") (pin "60") (pinfunction "I/O_60") (pintype "bidirectional"))
      (node (ref "DD4") (pin "11") (pinfunction "B7_11") (pintype "bidirectional"))
      (node (ref "DD6") (pin "9") (pinfunction "A13_9") (pintype "input"))
    )
    (net (code "86") (name "/VA14") (class "Default")
      (node (ref "DD2") (pin "76") (pinfunction "I/O_76") (pintype "bidirectional"))
      (node (ref "DD6") (pin "10") (pinfunction "A14_10") (pintype "input"))
    )
    (net (code "87") (name "/VAGEN") (class "Default")
      (node (ref "DD10") (pin "19") (pinfunction "~{OE}_19") (pintype "input"))
      (node (ref "DD2") (pin "10") (pinfunction "I/O_10") (pintype "bidirectional"))
      (node (ref "DD4") (pin "19") (pinfunction "~{OE}_19") (pintype "input"))
      (node (ref "DD5") (pin "19") (pinfunction "~{OE}_19") (pintype "input"))
    )
    (net (code "88") (name "/VD0") (class "Default")
      (node (ref "DD10") (pin "13") (pinfunction "B5_13") (pintype "bidirectional"))
      (node (ref "DD2") (pin "68") (pinfunction "I/O_68") (pintype "bidirectional"))
      (node (ref "DD6") (pin "11") (pinfunction "D0_11") (pintype "bidirectional"))
    )
    (net (code "89") (name "/VD1") (class "Default")
      (node (ref "DD10") (pin "12") (pinfunction "B6_12") (pintype "bidirectional"))
      (node (ref "DD2") (pin "69") (pinfunction "I/O_69") (pintype "bidirectional"))
      (node (ref "DD6") (pin "12") (pinfunction "D1_12") (pintype "bidirectional"))
    )
    (net (code "90") (name "/VD2") (class "Default")
      (node (ref "DD10") (pin "11") (pinfunction "B7_11") (pintype "bidirectional"))
      (node (ref "DD2") (pin "70") (pinfunction "I/O_70") (pintype "bidirectional"))
      (node (ref "DD6") (pin "13") (pinfunction "D2_13") (pintype "bidirectional"))
    )
    (net (code "91") (name "/VD3") (class "Default")
      (node (ref "DD10") (pin "14") (pinfunction "B4_14") (pintype "bidirectional"))
      (node (ref "DD2") (pin "61") (pinfunction "I/O_61") (pintype "bidirectional"))
      (node (ref "DD6") (pin "15") (pinfunction "D3_15") (pintype "bidirectional"))
    )
    (net (code "92") (name "/VD4") (class "Default")
      (node (ref "DD10") (pin "15") (pinfunction "B3_15") (pintype "bidirectional"))
      (node (ref "DD2") (pin "63") (pinfunction "I/O_63") (pintype "bidirectional"))
      (node (ref "DD6") (pin "16") (pinfunction "D4_16") (pintype "bidirectional"))
    )
    (net (code "93") (name "/VD5") (class "Default")
      (node (ref "DD10") (pin "16") (pinfunction "B2_16") (pintype "bidirectional"))
      (node (ref "DD2") (pin "64") (pinfunction "I/O_64") (pintype "bidirectional"))
      (node (ref "DD6") (pin "17") (pinfunction "D5_17") (pintype "bidirectional"))
    )
    (net (code "94") (name "/VD6") (class "Default")
      (node (ref "DD10") (pin "17") (pinfunction "B1_17") (pintype "bidirectional"))
      (node (ref "DD2") (pin "65") (pinfunction "I/O_65") (pintype "bidirectional"))
      (node (ref "DD6") (pin "18") (pinfunction "D6_18") (pintype "bidirectional"))
    )
    (net (code "95") (name "/VD7") (class "Default")
      (node (ref "DD10") (pin "18") (pinfunction "B0_18") (pintype "bidirectional"))
      (node (ref "DD2") (pin "67") (pinfunction "I/O_67") (pintype "bidirectional"))
      (node (ref "DD6") (pin "19") (pinfunction "D7_19") (pintype "bidirectional"))
    )
    (net (code "96") (name "/VRAM") (class "Default")
      (node (ref "DD2") (pin "58") (pinfunction "I/O_58") (pintype "bidirectional"))
      (node (ref "DD6") (pin "20") (pinfunction "~{CE}_20") (pintype "input"))
    )
    (net (code "97") (name "/VRD") (class "Default")
      (node (ref "DD2") (pin "54") (pinfunction "I/O_54") (pintype "bidirectional"))
      (node (ref "DD6") (pin "22") (pinfunction "~{OE}_22") (pintype "input"))
    )
    (net (code "98") (name "/VWR") (class "Default")
      (node (ref "DD2") (pin "41") (pinfunction "I/O_41") (pintype "bidirectional"))
      (node (ref "DD6") (pin "27") (pinfunction "~{WE}_27") (pintype "input"))
    )
    (net (code "99") (name "/WAIT_CPU") (class "Default")
      (node (ref "DD1") (pin "24") (pinfunction "WAIT_24") (pintype "input"))
      (node (ref "DD2") (pin "17") (pinfunction "I/O_17") (pintype "bidirectional"))
    )
    (net (code "100") (name "/WR") (class "Default")
      (node (ref "DD1") (pin "22") (pinfunction "~{WR}_22") (pintype "output"))
      (node (ref "DD2") (pin "8") (pinfunction "I/O_8") (pintype "bidirectional"))
      (node (ref "DD3") (pin "29") (pinfunction "~{WE}_29") (pintype "input"))
      (node (ref "DD7") (pin "18") (pinfunction "PD4(OC1B)_18") (pintype "passive"))
    )
    (net (code "101") (name "GND") (class "Default")
      (node (ref "C1") (pin "MINUS") (pinfunction "MINUS_MINUS") (pintype "passive"))
      (node (ref "C10") (pin "2") (pinfunction "2_2") (pintype "passive"))
      (node (ref "C11") (pin "2") (pinfunction "2_2") (pintype "passive"))
      (node (ref "C12") (pin "2") (pinfunction "2_2") (pintype "passive"))
      (node (ref "C2") (pin "2") (pinfunction "2_2") (pintype "passive"))
      (node (ref "C3") (pin "2") (pinfunction "2_2") (pintype "passive"))
      (node (ref "C4") (pin "2") (pinfunction "2_2") (pintype "passive"))
      (node (ref "C5") (pin "2") (pinfunction "2_2") (pintype "passive"))
      (node (ref "C6") (pin "2") (pinfunction "2_2") (pintype "passive"))
      (node (ref "C7") (pin "2") (pinfunction "2_2") (pintype "passive"))
      (node (ref "C8") (pin "2") (pinfunction "2_2") (pintype "passive"))
      (node (ref "C9") (pin "MINUS") (pinfunction "MINUS_MINUS") (pintype "passive"))
      (node (ref "DA1") (pin "2") (pinfunction "GND_2") (pintype "power_in"))
      (node (ref "DD1") (pin "29") (pinfunction "GND_29") (pintype "power_in"))
      (node (ref "DD10") (pin "10") (pinfunction "GND_10") (pintype "power_in"))
      (node (ref "DD11") (pin "7") (pinfunction "GND_7") (pintype "power_in"))
      (node (ref "DD2") (pin "19") (pinfunction "GND_19") (pintype "power_in"))
      (node (ref "DD2") (pin "32") (pinfunction "GND_32") (pintype "power_in"))
      (node (ref "DD2") (pin "42") (pinfunction "GND_42") (pintype "power_in"))
      (node (ref "DD2") (pin "47") (pinfunction "GND_47") (pintype "power_in"))
      (node (ref "DD2") (pin "59") (pinfunction "GND_59") (pintype "power_in"))
      (node (ref "DD2") (pin "7") (pinfunction "GND_7") (pintype "power_in"))
      (node (ref "DD2") (pin "72") (pinfunction "GND_72") (pintype "power_in"))
      (node (ref "DD2") (pin "82") (pinfunction "GND_82") (pintype "power_in"))
      (node (ref "DD3") (pin "16") (pinfunction "GND_16") (pintype "power_in"))
      (node (ref "DD4") (pin "10") (pinfunction "GND_10") (pintype "power_in"))
      (node (ref "DD5") (pin "10") (pinfunction "GND_10") (pintype "power_in"))
      (node (ref "DD6") (pin "14") (pinfunction "GND_14") (pintype "power_in"))
      (node (ref "DD7") (pin "11") (pinfunction "GND_11") (pintype "passive"))
      (node (ref "DD7") (pin "31") (pinfunction "GND_31") (pintype "passive"))
      (node (ref "DD8") (pin "16") (pinfunction "GND_16") (pintype "power_in"))
      (node (ref "DD8") (pin "2") (pinfunction "A16_2") (pintype "input"))
      (node (ref "DD8") (pin "30") (pinfunction "A17_30") (pintype "input"))
      (node (ref "DD9") (pin "1") (pinfunction "GND_1") (pintype "power_in"))
      (node (ref "DD9") (pin "24") (pinfunction "CS2_24") (pintype "passive"))
      (node (ref "Q1") (pin "1") (pinfunction "e_1") (pintype "passive"))
      (node (ref "R12") (pin "2") (pinfunction "2_2") (pintype "passive"))
      (node (ref "R14") (pin "2") (pinfunction "2_2") (pintype "passive"))
      (node (ref "R18") (pin "1") (pinfunction "1_1") (pintype "passive"))
      (node (ref "R2") (pin "2") (pinfunction "2_2") (pintype "passive"))
      (node (ref "R29") (pin "2") (pinfunction "2_2") (pintype "passive"))
      (node (ref "R32") (pin "2") (pinfunction "2_2") (pintype "passive"))
      (node (ref "X1") (pin "1") (pinfunction "CON_1") (pintype "passive"))
      (node (ref "X2") (pin "3") (pinfunction "CON_3") (pintype "passive"))
      (node (ref "X3") (pin "4") (pinfunction "CON_4") (pintype "passive"))
      (node (ref "X4") (pin "3") (pinfunction "CON_3") (pintype "passive"))
      (node (ref "X4") (pin "6") (pinfunction "CON_6") (pintype "passive"))
      (node (ref "X6") (pin "10") (pinfunction "CON_10") (pintype "passive"))
      (node (ref "X6") (pin "2") (pinfunction "CON_2") (pintype "passive"))
      (node (ref "X7") (pin "10") (pinfunction "CON_10") (pintype "passive"))
    )
    (net (code "102") (name "Net-(C13-PadMINUS)") (class "Default")
      (node (ref "C13") (pin "MINUS") (pinfunction "MINUS_MINUS") (pintype "passive"))
      (node (ref "R25") (pin "2") (pinfunction "2_2") (pintype "passive"))
      (node (ref "R26") (pin "2") (pinfunction "2_2") (pintype "passive"))
      (node (ref "R29") (pin "1") (pinfunction "1_1") (pintype "passive"))
      (node (ref "R30") (pin "1") (pinfunction "1_1") (pintype "passive"))
    )
    (net (code "103") (name "Net-(C14-PadMINUS)") (class "Default")
      (node (ref "C14") (pin "MINUS") (pinfunction "MINUS_MINUS") (pintype "passive"))
      (node (ref "R27") (pin "2") (pinfunction "2_2") (pintype "passive"))
      (node (ref "R28") (pin "2") (pinfunction "2_2") (pintype "passive"))
      (node (ref "R31") (pin "1") (pinfunction "1_1") (pintype "passive"))
      (node (ref "R32") (pin "1") (pinfunction "1_1") (pintype "passive"))
    )
    (net (code "104") (name "Net-(C15-Pad1)") (class "Default")
      (node (ref "C15") (pin "1") (pinfunction "1_1") (pintype "passive"))
      (node (ref "R30") (pin "2") (pinfunction "2_2") (pintype "passive"))
      (node (ref "R31") (pin "2") (pinfunction "2_2") (pintype "passive"))
    )
    (net (code "105") (name "Net-(C15-Pad2)") (class "Default")
      (node (ref "C15") (pin "2") (pinfunction "2_2") (pintype "passive"))
      (node (ref "R33") (pin "1") (pinfunction "1_1") (pintype "passive"))
    )
    (net (code "106") (name "Net-(DA1-OUT)") (class "Default")
      (node (ref "C8") (pin "1") (pinfunction "1_1") (pintype "passive"))
      (node (ref "C9") (pin "PLUS") (pinfunction "PLUS_PLUS") (pintype "passive"))
      (node (ref "DA1") (pin "1") (pinfunction "OUT_1") (pintype "output"))
      (node (ref "R11") (pin "1") (pinfunction "1_1") (pintype "passive"))
      (node (ref "R16") (pin "2") (pinfunction "2_2") (pintype "passive"))
      (node (ref "X4") (pin "4") (pinfunction "CON_4") (pintype "passive"))
    )
    (net (code "107") (name "Net-(DD9-A)") (class "Default")
      (node (ref "DD9") (pin "4") (pinfunction "A_4") (pintype "passive"))
      (node (ref "R25") (pin "1") (pinfunction "1_1") (pintype "passive"))
    )
    (net (code "108") (name "Net-(DD9-B)") (class "Default")
      (node (ref "DD9") (pin "3") (pinfunction "B_3") (pintype "passive"))
      (node (ref "R26") (pin "1") (pinfunction "1_1") (pintype "passive"))
      (node (ref "R27") (pin "1") (pinfunction "1_1") (pintype "passive"))
    )
    (net (code "109") (name "Net-(DD9-C)") (class "Default")
      (node (ref "DD9") (pin "38") (pinfunction "C_38") (pintype "passive"))
      (node (ref "R28") (pin "1") (pinfunction "1_1") (pintype "passive"))
    )
    (net (code "110") (name "Net-(DD11A-A)") (class "Default")
      (node (ref "DD11") (pin "1") (pinfunction "A_1") (pintype "input"))
      (node (ref "R34") (pin "1") (pinfunction "1_1") (pintype "passive"))
      (node (ref "ZQ1") (pin "1") (pinfunction "1_1") (pintype "passive"))
    )
    (net (code "111") (name "Net-(DD11A-Y)") (class "Default")
      (node (ref "DD11") (pin "2") (pinfunction "Y_2") (pintype "output"))
      (node (ref "DD11") (pin "3") (pinfunction "A_3") (pintype "input"))
      (node (ref "R34") (pin "2") (pinfunction "2_2") (pintype "passive"))
    )
    (net (code "112") (name "Net-(DD11B-Y)") (class "Default")
      (node (ref "DD11") (pin "4") (pinfunction "Y_4") (pintype "output"))
      (node (ref "DD11") (pin "5") (pinfunction "A_5") (pintype "input"))
      (node (ref "ZQ1") (pin "2") (pinfunction "2_2") (pintype "passive"))
    )
    (net (code "113") (name "Net-(Q1-b)") (class "Default")
      (node (ref "Q1") (pin "2") (pinfunction "b_2") (pintype "passive"))
      (node (ref "R17") (pin "1") (pinfunction "1_1") (pintype "passive"))
      (node (ref "R18") (pin "2") (pinfunction "2_2") (pintype "passive"))
    )
    (net (code "114") (name "Net-(Q1-c)") (class "Default")
      (node (ref "Q1") (pin "3") (pinfunction "c_3") (pintype "passive"))
      (node (ref "R16") (pin "1") (pinfunction "1_1") (pintype "passive"))
      (node (ref "X4") (pin "1") (pinfunction "CON_1") (pintype "passive"))
    )
    (net (code "115") (name "Net-(SW1-NC)") (class "Default")
      (node (ref "SW1") (pin "1") (pinfunction "NC_1") (pintype "passive"))
      (node (ref "X1") (pin "3") (pinfunction "CON_3") (pintype "passive"))
    )
    (net (code "116") (name "Net-(X3C-CON)") (class "Default")
      (node (ref "R3") (pin "2") (pinfunction "2_2") (pintype "passive"))
      (node (ref "X3") (pin "3") (pinfunction "CON_3") (pintype "passive"))
    )
    (net (code "117") (name "Net-(X3E-CON)") (class "Default")
      (node (ref "R4") (pin "2") (pinfunction "2_2") (pintype "passive"))
      (node (ref "X3") (pin "5") (pinfunction "CON_5") (pintype "passive"))
    )
    (net (code "118") (name "Net-(X3F-CON)") (class "Default")
      (node (ref "R5") (pin "2") (pinfunction "2_2") (pintype "passive"))
      (node (ref "R8") (pin "2") (pinfunction "2_2") (pintype "passive"))
      (node (ref "X3") (pin "6") (pinfunction "CON_6") (pintype "passive"))
    )
    (net (code "119") (name "Net-(X3G-CON)") (class "Default")
      (node (ref "R6") (pin "2") (pinfunction "2_2") (pintype "passive"))
      (node (ref "R9") (pin "2") (pinfunction "2_2") (pintype "passive"))
      (node (ref "X3") (pin "7") (pinfunction "CON_7") (pintype "passive"))
    )
    (net (code "120") (name "Net-(X3H-CON)") (class "Default")
      (node (ref "R10") (pin "2") (pinfunction "2_2") (pintype "passive"))
      (node (ref "R7") (pin "2") (pinfunction "2_2") (pintype "passive"))
      (node (ref "X3") (pin "8") (pinfunction "CON_8") (pintype "passive"))
    )
    (net (code "121") (name "Net-(X4B-CON)") (class "Default")
      (node (ref "R14") (pin "1") (pinfunction "1_1") (pintype "passive"))
      (node (ref "R15") (pin "2") (pinfunction "2_2") (pintype "passive"))
      (node (ref "X4") (pin "2") (pinfunction "CON_2") (pintype "passive"))
    )
    (net (code "122") (name "Net-(X4E-CON)") (class "Default")
      (node (ref "R12") (pin "1") (pinfunction "1_1") (pintype "passive"))
      (node (ref "R13") (pin "2") (pinfunction "2_2") (pintype "passive"))
      (node (ref "X4") (pin "5") (pinfunction "CON_5") (pintype "passive"))
    )
    (net (code "123") (name "VCC") (class "Default")
      (node (ref "C1") (pin "PLUS") (pinfunction "PLUS_PLUS") (pintype "passive"))
      (node (ref "C10") (pin "1") (pinfunction "1_1") (pintype "passive"))
      (node (ref "C11") (pin "1") (pinfunction "1_1") (pintype "passive"))
      (node (ref "C12") (pin "1") (pinfunction "1_1") (pintype "passive"))
      (node (ref "C2") (pin "1") (pinfunction "1_1") (pintype "passive"))
      (node (ref "C3") (pin "1") (pinfunction "1_1") (pintype "passive"))
      (node (ref "C4") (pin "1") (pinfunction "1_1") (pintype "passive"))
      (node (ref "C5") (pin "1") (pinfunction "1_1") (pintype "passive"))
      (node (ref "C6") (pin "1") (pinfunction "1_1") (pintype "passive"))
      (node (ref "C7") (pin "1") (pinfunction "1_1") (pintype "passive"))
      (node (ref "DA1") (pin "3") (pinfunction "IN_3") (pintype "input"))
      (node (ref "DD1") (pin "11") (pinfunction "VCC_11") (pintype "power_in"))
      (node (ref "DD10") (pin "1") (pinfunction "DIR_1") (pintype "input"))
      (node (ref "DD10") (pin "20") (pinfunction "VCC_20") (pintype "power_in"))
      (node (ref "DD11") (pin "14") (pinfunction "VCC_14") (pintype "power_in"))
      (node (ref "DD2") (pin "13") (pinfunction "VCCIO_13") (pintype "power_in"))
      (node (ref "DD2") (pin "26") (pinfunction "VCCIO_26") (pintype "power_in"))
      (node (ref "DD2") (pin "3") (pinfunction "VCC_3") (pintype "power_in"))
      (node (ref "DD2") (pin "38") (pinfunction "VCCIO_38") (pintype "power_in"))
      (node (ref "DD2") (pin "43") (pinfunction "VCC_43") (pintype "power_in"))
      (node (ref "DD2") (pin "53") (pinfunction "VCCIO_53") (pintype "power_in"))
      (node (ref "DD2") (pin "66") (pinfunction "VCCIO_66") (pintype "power_in"))
      (node (ref "DD2") (pin "78") (pinfunction "VCCIO_78") (pintype "power_in"))
      (node (ref "DD3") (pin "30") (pinfunction "CS2_30") (pintype "input"))
      (node (ref "DD3") (pin "32") (pinfunction "VCC_32") (pintype "power_in"))
      (node (ref "DD4") (pin "1") (pinfunction "DIR_1") (pintype "input"))
      (node (ref "DD4") (pin "20") (pinfunction "VCC_20") (pintype "power_in"))
      (node (ref "DD5") (pin "1") (pinfunction "DIR_1") (pintype "input"))
      (node (ref "DD5") (pin "20") (pinfunction "VCC_20") (pintype "power_in"))
      (node (ref "DD5") (pin "8") (pinfunction "A6_8") (pintype "bidirectional"))
      (node (ref "DD5") (pin "9") (pinfunction "A7_9") (pintype "bidirectional"))
      (node (ref "DD6") (pin "28") (pinfunction "VCC_28") (pintype "power_in"))
      (node (ref "DD7") (pin "10") (pinfunction "VCC_10") (pintype "passive"))
      (node (ref "DD7") (pin "30") (pinfunction "AVCC_30") (pintype "passive"))
      (node (ref "DD8") (pin "31") (pinfunction "~{WE}_31") (pintype "input"))
      (node (ref "DD8") (pin "32") (pinfunction "VCC_32") (pintype "power_in"))
      (node (ref "DD9") (pin "25") (pinfunction "CS1_25") (pintype "passive"))
      (node (ref "DD9") (pin "28") (pinfunction "BC2_28") (pintype "passive"))
      (node (ref "DD9") (pin "40") (pinfunction "VCC_40") (pintype "power_in"))
      (node (ref "R19") (pin "1") (pinfunction "1_1") (pintype "passive"))
      (node (ref "R20") (pin "1") (pinfunction "1_1") (pintype "passive"))
      (node (ref "R21") (pin "1") (pinfunction "1_1") (pintype "passive"))
      (node (ref "R22") (pin "1") (pinfunction "1_1") (pintype "passive"))
      (node (ref "R23") (pin "1") (pinfunction "1_1") (pintype "passive"))
      (node (ref "R24") (pin "1") (pinfunction "1_1") (pintype "passive"))
      (node (ref "R3") (pin "1") (pinfunction "1_1") (pintype "passive"))
      (node (ref "SW1") (pin "2") (pinfunction "COMMON_2") (pintype "passive"))
      (node (ref "X2") (pin "4") (pinfunction "CON_4") (pintype "passive"))
      (node (ref "X6") (pin "4") (pinfunction "CON_4") (pintype "passive"))
      (node (ref "X7") (pin "2") (pinfunction "CON_2") (pintype "passive"))
    )
    (net (code "124") (name "unconnected-(DD1-~{BUSAK}-Pad23)") (class "Default")
      (node (ref "DD1") (pin "23") (pinfunction "~{BUSAK}_23") (pintype "output"))
    )
    (net (code "125") (name "unconnected-(DD1-~{HALT}-Pad18)") (class "Default")
      (node (ref "DD1") (pin "18") (pinfunction "~{HALT}_18") (pintype "output"))
    )
    (net (code "126") (name "unconnected-(DD1-~{REFSH}-Pad28)") (class "Default")
      (node (ref "DD1") (pin "28") (pinfunction "~{REFSH}_28") (pintype "output"))
    )
    (net (code "127") (name "unconnected-(DD2-I{slash}~{OE1}-Pad84)") (class "Default")
      (node (ref "DD2") (pin "84") (pinfunction "I/~{OE1}_84") (pintype "input"))
    )
    (net (code "128") (name "unconnected-(DD5-B6-Pad12)") (class "Default")
      (node (ref "DD5") (pin "12") (pinfunction "B6_12") (pintype "bidirectional"))
    )
    (net (code "129") (name "unconnected-(DD5-B7-Pad11)") (class "Default")
      (node (ref "DD5") (pin "11") (pinfunction "B7_11") (pintype "bidirectional"))
    )
    (net (code "130") (name "unconnected-(DD7-AREF-Pad32)") (class "Default")
      (node (ref "DD7") (pin "32") (pinfunction "AREF_32") (pintype "passive"))
    )
    (net (code "131") (name "unconnected-(DD7-XTAL2-Pad12)") (class "Default")
      (node (ref "DD7") (pin "12") (pinfunction "XTAL2_12") (pintype "passive"))
    )
    (net (code "132") (name "unconnected-(DD9-MOD-Pad26)") (class "Default")
      (node (ref "DD9") (pin "26") (pinfunction "MOD_26") (pintype "passive"))
    )
    (net (code "133") (name "unconnected-(SW1-NO-Pad3)") (class "Default")
      (node (ref "SW1") (pin "3") (pinfunction "NO_3") (pintype "passive"))
    )
    (net (code "134") (name "unconnected-(X1B-CON-Pad2)") (class "Default")
      (node (ref "X1") (pin "2") (pinfunction "CON_2") (pintype "passive"))
    )
    (net (code "135") (name "unconnected-(X2B-CON-Pad2)") (class "Default")
      (node (ref "X2") (pin "2") (pinfunction "CON_2") (pintype "passive"))
    )
    (net (code "136") (name "unconnected-(X2F-CON-Pad6)") (class "Default")
      (node (ref "X2") (pin "6") (pinfunction "CON_6") (pintype "passive"))
    )
    (net (code "137") (name "unconnected-(X4H-CON-Pad8)") (class "Default")
      (node (ref "X4") (pin "8") (pinfunction "CON_8") (pintype "passive"))
    )
    (net (code "138") (name "unconnected-(X4I-CON-Pad9)") (class "Default")
      (node (ref "X4") (pin "9") (pinfunction "CON_9") (pintype "passive"))
    )
    (net (code "139") (name "unconnected-(X6F-CON-Pad6)") (class "Default")
      (node (ref "X6") (pin "6") (pinfunction "CON_6") (pintype "passive"))
    )
    (net (code "140") (name "unconnected-(X6G-CON-Pad7)") (class "Default")
      (node (ref "X6") (pin "7") (pinfunction "CON_7") (pintype "passive"))
    )
    (net (code "141") (name "unconnected-(X6H-CON-Pad8)") (class "Default")
      (node (ref "X6") (pin "8") (pinfunction "CON_8") (pintype "passive"))
    )
    (net (code "142") (name "unconnected-(X7C-CON-Pad3)") (class "Default")
      (node (ref "X7") (pin "3") (pinfunction "CON_3") (pintype "passive"))
    )
    (net (code "143") (name "unconnected-(X7D-CON-Pad4)") (class "Default")
      (node (ref "X7") (pin "4") (pinfunction "CON_4") (pintype "passive"))
    )
    (net (code "144") (name "unconnected-(X7F-CON-Pad6)") (class "Default")
      (node (ref "X7") (pin "6") (pinfunction "CON_6") (pintype "passive"))
    )
    (net (code "145") (name "unconnected-(X7H-CON-Pad8)") (class "Default")
      (node (ref "X7") (pin "8") (pinfunction "CON_8") (pintype "passive"))
    )
  )
)
